# 03_ETHERNET_1_Gbps.net
KiCad netlist of a schematic drawn in Altium Designer
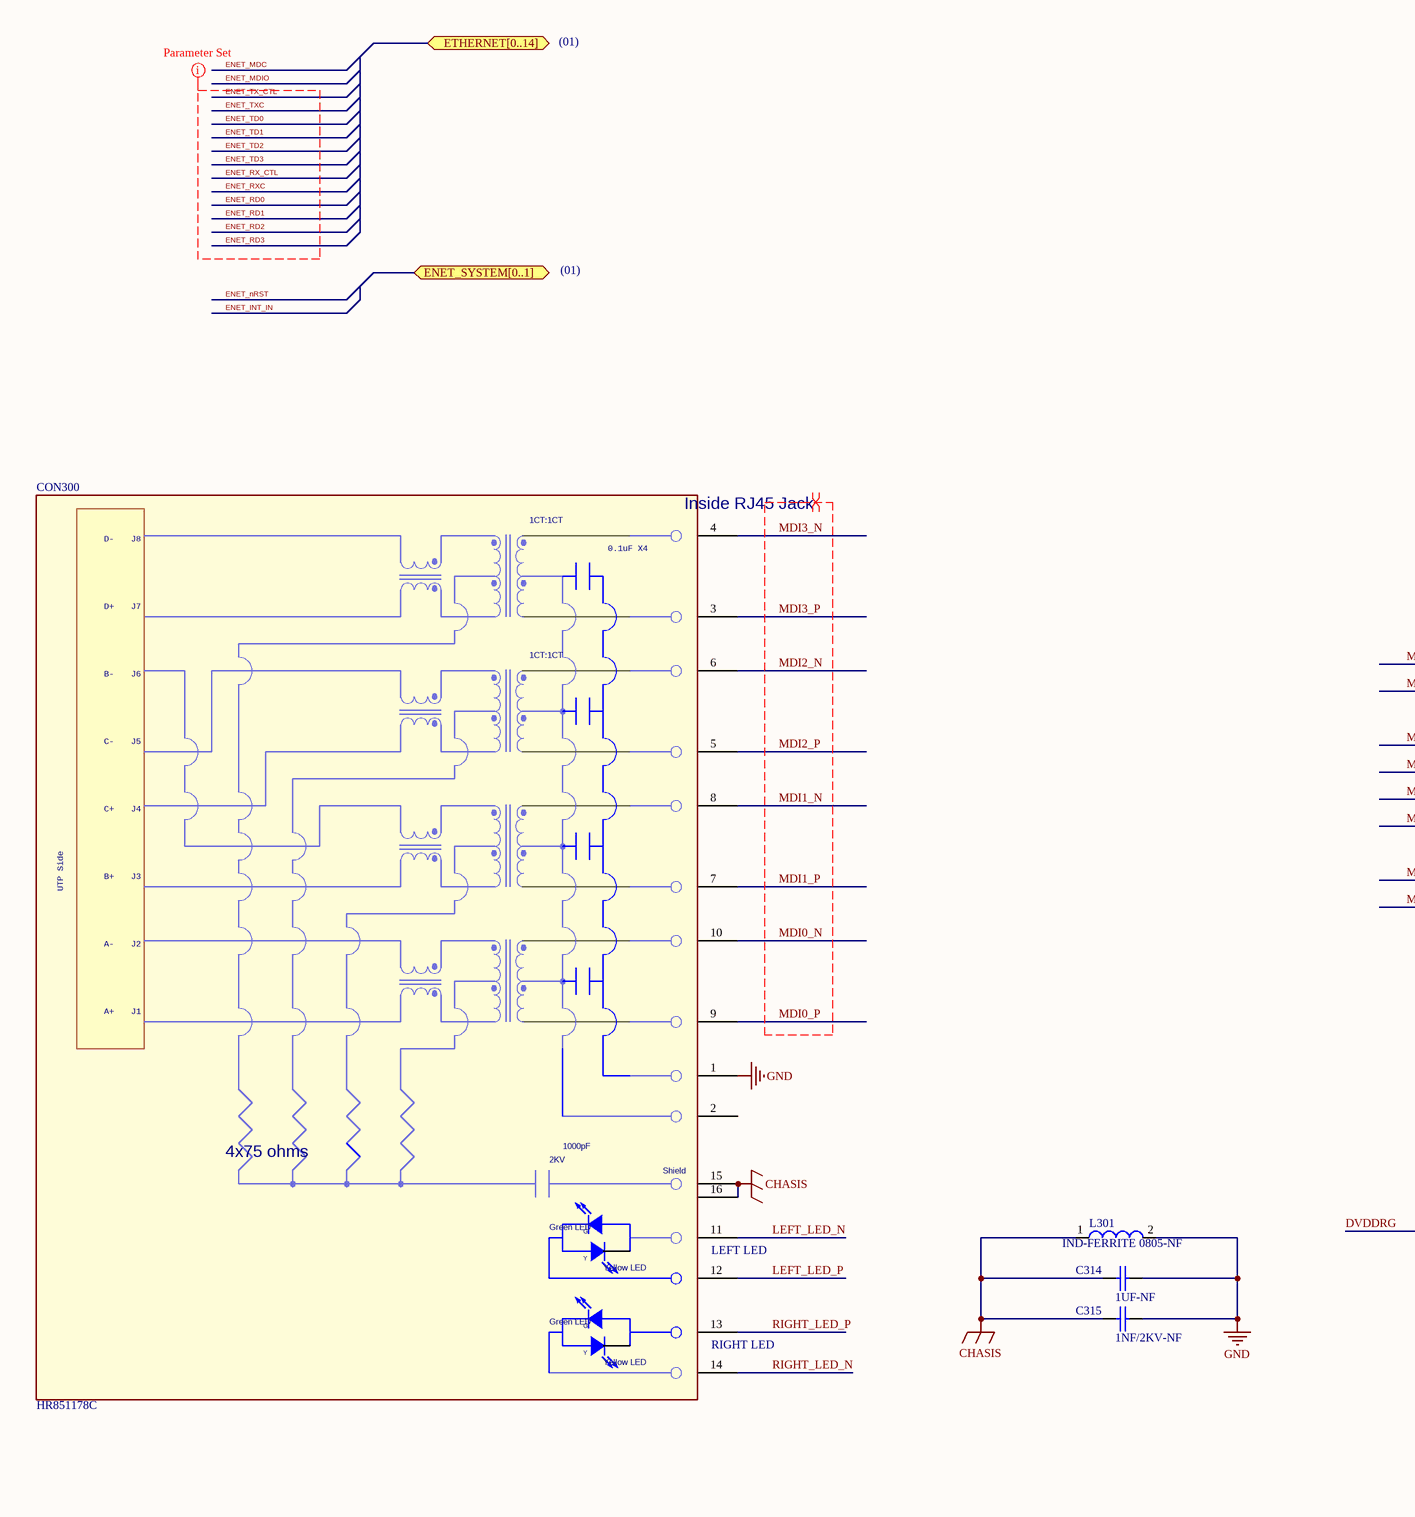
[diagram p0: 03 ETHERNET 1 Gbps.SchDoc, left]
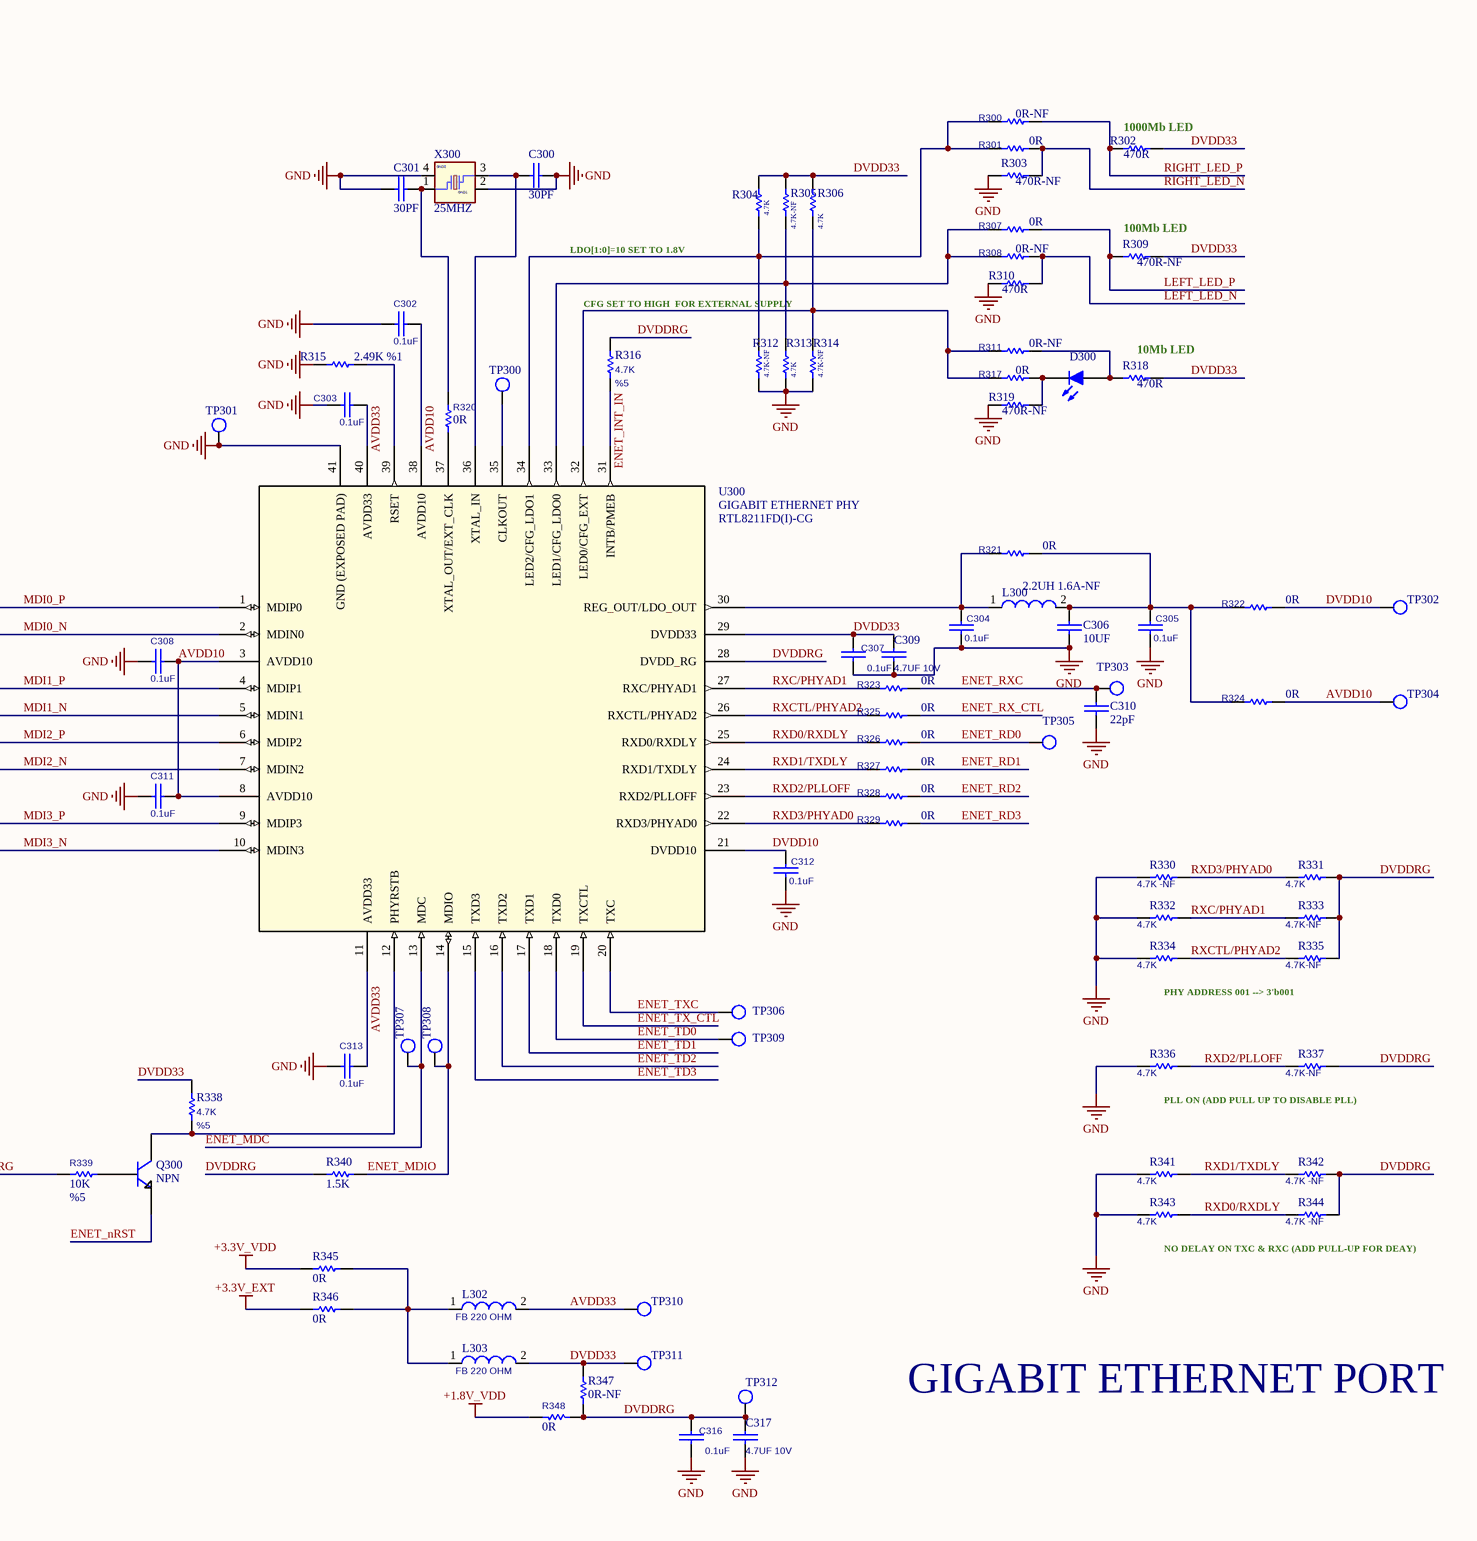
[diagram p1: 03 ETHERNET 1 Gbps.SchDoc, right]

(export (version "E")
  (design (tool "Eeschema 10.0.6"))
  (components
    (comp (ref "C300")
      (value "30PF")
      (footprint "0402_CC")
      (description "CAP CER 30PF 50V 5% C0G/NPO 0402")
      (fields (field (name "CREATED BY") "*") (field (name "CHECKED BY") "*"))
      (libsource (lib "ARETE_SCH") (part "CAP-CC0402JRNPO9BN300"))
    )
    (comp (ref "C301")
      (value "30PF")
      (footprint "0402_CC")
      (description "CAP CER 30PF 50V 5% C0G/NPO 0402")
      (fields (field (name "CREATED BY") "*") (field (name "CHECKED BY") "*"))
      (libsource (lib "ARETE_SCH") (part "CAP-CC0402JRNPO9BN300"))
    )
    (comp (ref "C302")
      (value "0.1uF")
      (footprint "0402_CC")
      (description "CAP VER 0.1UF 16V X7R 0402")
      (fields (field (name "CREATED BY") "LA") (field (name "CHECKED BY") "*"))
      (libsource (lib "ARETE_SCH") (part "CAP-CL05B104KO5NNNC"))
    )
    (comp (ref "C303")
      (value "0.1uF")
      (footprint "0402_CC")
      (description "CAP VER 0.1UF 16V X7R 0402")
      (fields (field (name "CREATED BY") "LA") (field (name "CHECKED BY") "*"))
      (libsource (lib "ARETE_SCH") (part "CAP-CL05B104KO5NNNC"))
    )
    (comp (ref "C304")
      (value "0.1uF")
      (footprint "0402_CC")
      (description "CAP VER 0.1UF 16V X7R 0402")
      (fields (field (name "CREATED BY") "LA") (field (name "CHECKED BY") "*"))
      (libsource (lib "ARETE_SCH") (part "CAP-CL05B104KO5NNNC"))
    )
    (comp (ref "C305")
      (value "0.1uF")
      (footprint "0402_CC")
      (description "CAP VER 0.1UF 16V X7R 0402")
      (fields (field (name "CREATED BY") "LA") (field (name "CHECKED BY") "*"))
      (libsource (lib "ARETE_SCH") (part "CAP-CL05B104KO5NNNC"))
    )
    (comp (ref "C306")
      (value "10UF")
      (footprint "0805")
      (description "CAP CER 10UF 6.3V X7R 0805")
      (fields (field (name "CREATED BY") "LA") (field (name "CHECKED BY") "*"))
      (libsource (lib "ARETE_SCH") (part "CAP-C0805C106M9RACAUTO"))
    )
    (comp (ref "C307")
      (value "0.1uF")
      (footprint "0402_CC")
      (description "CAP VER 0.1UF 16V X7R 0402")
      (fields (field (name "CREATED BY") "LA") (field (name "CHECKED BY") "*"))
      (libsource (lib "ARETE_SCH") (part "CAP-CL05B104KO5NNNC"))
    )
    (comp (ref "C308")
      (value "0.1uF")
      (footprint "0402_CC")
      (description "CAP VER 0.1UF 16V X7R 0402")
      (fields (field (name "CREATED BY") "LA") (field (name "CHECKED BY") "*"))
      (libsource (lib "ARETE_SCH") (part "CAP-CL05B104KO5NNNC"))
    )
    (comp (ref "C309")
      (value "4.7UF 10V")
      (footprint "0402_CC")
      (description "CAP CER 4.7UF 10V X5R 0402")
      (fields (field (name "CREATED BY") "EE") (field (name "CHECKED BY") "*"))
      (libsource (lib "ARETE_SCH") (part "CAP-CL05A475MP5NRNC"))
    )
    (comp (ref "C310")
      (value "22pF")
      (footprint "0402_CC")
      (description "CAP CER 22PF 50V C0G/NPO 0402")
      (fields (field (name "CREATED BY") "LA") (field (name "CHECKED BY") "*"))
      (libsource (lib "ARETE_SCH") (part "CAP-C0402C220K5GACTU"))
    )
    (comp (ref "C311")
      (value "0.1uF")
      (footprint "0402_CC")
      (description "CAP VER 0.1UF 16V X7R 0402")
      (fields (field (name "CREATED BY") "LA") (field (name "CHECKED BY") "*"))
      (libsource (lib "ARETE_SCH") (part "CAP-CL05B104KO5NNNC"))
    )
    (comp (ref "C312")
      (value "0.1uF")
      (footprint "0402_CC")
      (description "CAP VER 0.1UF 16V X7R 0402")
      (fields (field (name "CREATED BY") "LA") (field (name "CHECKED BY") "*"))
      (libsource (lib "ARETE_SCH") (part "CAP-CL05B104KO5NNNC"))
    )
    (comp (ref "C313")
      (value "0.1uF")
      (footprint "0402_CC")
      (description "CAP VER 0.1UF 16V X7R 0402")
      (fields (field (name "CREATED BY") "LA") (field (name "CHECKED BY") "*"))
      (libsource (lib "ARETE_SCH") (part "CAP-CL05B104KO5NNNC"))
    )
    (comp (ref "C314")
      (value "1UF-NF")
      (footprint "0805")
      (description "CAP CER 1UF 50V X7R 0805")
      (fields (field (name "CREATED BY") "*") (field (name "CHECKED BY") "*"))
      (libsource (lib "ARETE_SCH") (part "CAP-CL21B105KBFNNNG"))
    )
    (comp (ref "C315")
      (value "1NF/2KV-NF")
      (footprint "1206")
      (description "CAP CER 1NF 2KV 10% X7R SMD 1206")
      (fields (field (name "CREATED BY") "OKS") (field (name "CHECKED BY") "*"))
      (libsource (lib "ARETE_SCH") (part "CAP-1206GC102KAT2A"))
    )
    (comp (ref "C316")
      (value "0.1uF")
      (footprint "0402_CC")
      (description "CAP VER 0.1UF 16V X7R 0402")
      (fields (field (name "CREATED BY") "LA") (field (name "CHECKED BY") "*"))
      (libsource (lib "ARETE_SCH") (part "CAP-CL05B104KO5NNNC"))
    )
    (comp (ref "C317")
      (value "4.7UF 10V")
      (footprint "0402_CC")
      (description "CAP CER 4.7UF 10V X5R 0402")
      (fields (field (name "CREATED BY") "EE") (field (name "CHECKED BY") "*"))
      (libsource (lib "ARETE_SCH") (part "CAP-CL05A475MP5NRNC"))
    )
    (comp (ref "CON300")
      (value "HR851178C")
      (footprint "HR851178C")
      (description "GIGABIT ETHERNET CONN")
      (fields (field (name "CREATED BY") "EE") (field (name "CHECKED BY") "*"))
      (libsource (lib "ARETE_SCH") (part "CON-HR851178C"))
    )
    (comp (ref "D300")
      (value "GREEN")
      (footprint "0603_LED")
      (description "LED SMD 0603 SUPER GREEN")
      (fields (field (name "CREATED BY") "*") (field (name "CHECKED BY") "*"))
      (libsource (lib "ARETE_SCH") (part "LED-LTST-C190KRKT"))
    )
    (comp (ref "L300")
      (value "2.2UH 1.6A-NF")
      (footprint "2016")
      (description "FIXED IND 2.2UH 1.6A 154MOHM SMD")
      (fields (field (name "CREATED BY") "EE") (field (name "CHECKED BY") "*"))
      (libsource (lib "ARETE_V2_SCH") (part "IND-CIGT201610LM2R2MNE"))
    )
    (comp (ref "L301")
      (value "IND-FERRITE 0805-NF")
      (footprint "0805")
      (description "FERRITE BEAD 0805")
      (fields (field (name "CHECKED BY") "*"))
      (libsource (lib "ARETE_SCH") (part "IND-FERRITE 0805"))
    )
    (comp (ref "L302")
      (value "FB 220 OHM")
      (footprint "0603_RES")
      (description "Power Line Ferrite Bead 0603 (1608 Metric) 2.2A 50mOhmFERRITE BEAD 220 OHM 0603 1LN")
      (fields (field (name "CREATED BY") "E.E") (field (name "CHECKED BY") "*"))
      (libsource (lib "ARETE_SCH") (part "IND-MPZ1608S221ATA00"))
    )
    (comp (ref "L303")
      (value "FB 220 OHM")
      (footprint "0603_RES")
      (description "Power Line Ferrite Bead 0603 (1608 Metric) 2.2A 50mOhmFERRITE BEAD 220 OHM 0603 1LN")
      (fields (field (name "CREATED BY") "E.E") (field (name "CHECKED BY") "*"))
      (libsource (lib "ARETE_SCH") (part "IND-MPZ1608S221ATA00"))
    )
    (comp (ref "Q300")
      (value "NPN")
      (footprint "SOT23")
      (description "TRANS PNP 65V 0.1A SOT-23")
      (fields (field (name "CREATED BY") "LA") (field (name "CHECKED BY") "*"))
      (libsource (lib "ARETE_SCH") (part "TRANSISTOR-BC846"))
    )
    (comp (ref "R300")
      (value "0R-NF")
      (footprint "0402_RES")
      (description "RES 0 OHM JUMPER 1/16W 0402")
      (fields (field (name "CREATED BY") "LA") (field (name "CHECKED BY") "*"))
      (libsource (lib "ARETE_SCH") (part "RES-RMCF0402ZT0R00"))
    )
    (comp (ref "R301")
      (value "0R")
      (footprint "0402_RES")
      (description "RES 0 OHM JUMPER 1/16W 0402")
      (fields (field (name "CREATED BY") "LA") (field (name "CHECKED BY") "*"))
      (libsource (lib "ARETE_SCH") (part "RES-RMCF0402ZT0R00"))
    )
    (comp (ref "R302")
      (value "470R")
      (footprint "0402_RES")
      (description "RES SMD 470 OHM 1% 1/16W 0402")
      (fields
        (field (name "TOLERANCE") "%1")
        (field (name "CREATED BY") "LA")
        (field (name "CHECKED BY") "*")
      )
      (libsource (lib "ARETE_SCH") (part "RES-RC0402FR-07470R"))
    )
    (comp (ref "R303")
      (value "470R-NF")
      (footprint "0402_RES")
      (description "RES SMD 470 OHM 1% 1/16W 0402")
      (fields
        (field (name "TOLERANCE") "%1")
        (field (name "CREATED BY") "LA")
        (field (name "CHECKED BY") "*")
      )
      (libsource (lib "ARETE_SCH") (part "RES-RC0402FR-07470R"))
    )
    (comp (ref "R304")
      (value "4.7K")
      (footprint "0402_RES")
      (description "RES 4.7K OHM 5% 1/16W 0402")
      (fields
        (field (name "TOLERANCE") "%5")
        (field (name "CREATED BY") "LA")
        (field (name "CHECKED BY") "*")
      )
      (libsource (lib "ARETE_L") (part "RES-4.7K"))
    )
    (comp (ref "R305")
      (value "4.7K-NF")
      (footprint "0402_RES")
      (description "RES 4.7K OHM 5% 1/16W 0402")
      (fields
        (field (name "TOLERANCE") "%5")
        (field (name "CREATED BY") "LA")
        (field (name "CHECKED BY") "*")
      )
      (libsource (lib "ARETE_L") (part "RES-4.7K"))
    )
    (comp (ref "R306")
      (value "4.7K")
      (footprint "0402_RES")
      (description "RES 4.7K OHM 5% 1/16W 0402")
      (fields
        (field (name "TOLERANCE") "%5")
        (field (name "CREATED BY") "LA")
        (field (name "CHECKED BY") "*")
      )
      (libsource (lib "ARETE_L") (part "RES-4.7K"))
    )
    (comp (ref "R307")
      (value "0R")
      (footprint "0402_RES")
      (description "RES 0 OHM JUMPER 1/16W 0402")
      (fields (field (name "CREATED BY") "LA") (field (name "CHECKED BY") "*"))
      (libsource (lib "ARETE_SCH") (part "RES-RMCF0402ZT0R00"))
    )
    (comp (ref "R308")
      (value "0R-NF")
      (footprint "0402_RES")
      (description "RES 0 OHM JUMPER 1/16W 0402")
      (fields (field (name "CREATED BY") "LA") (field (name "CHECKED BY") "*"))
      (libsource (lib "ARETE_SCH") (part "RES-RMCF0402ZT0R00"))
    )
    (comp (ref "R309")
      (value "470R-NF")
      (footprint "0402_RES")
      (description "RES SMD 470 OHM 1% 1/16W 0402")
      (fields
        (field (name "TOLERANCE") "%1")
        (field (name "CREATED BY") "LA")
        (field (name "CHECKED BY") "*")
      )
      (libsource (lib "ARETE_SCH") (part "RES-RC0402FR-07470R"))
    )
    (comp (ref "R310")
      (value "470R")
      (footprint "0402_RES")
      (description "RES SMD 470 OHM 1% 1/16W 0402")
      (fields
        (field (name "TOLERANCE") "%1")
        (field (name "CREATED BY") "LA")
        (field (name "CHECKED BY") "*")
      )
      (libsource (lib "ARETE_SCH") (part "RES-RC0402FR-07470R"))
    )
    (comp (ref "R311")
      (value "0R-NF")
      (footprint "0402_RES")
      (description "RES 0 OHM JUMPER 1/16W 0402")
      (fields (field (name "CREATED BY") "LA") (field (name "CHECKED BY") "*"))
      (libsource (lib "ARETE_SCH") (part "RES-RMCF0402ZT0R00"))
    )
    (comp (ref "R312")
      (value "4.7K-NF")
      (footprint "0402_RES")
      (description "RES 4.7K OHM 5% 1/16W 0402")
      (fields
        (field (name "TOLERANCE") "%5")
        (field (name "CREATED BY") "LA")
        (field (name "CHECKED BY") "*")
      )
      (libsource (lib "ARETE_L") (part "RES-4.7K"))
    )
    (comp (ref "R313")
      (value "4.7K")
      (footprint "0402_RES")
      (description "RES 4.7K OHM 5% 1/16W 0402")
      (fields
        (field (name "TOLERANCE") "%5")
        (field (name "CREATED BY") "LA")
        (field (name "CHECKED BY") "*")
      )
      (libsource (lib "ARETE_L") (part "RES-4.7K"))
    )
    (comp (ref "R314")
      (value "4.7K-NF")
      (footprint "0402_RES")
      (description "RES 4.7K OHM 5% 1/16W 0402")
      (fields
        (field (name "TOLERANCE") "%5")
        (field (name "CREATED BY") "LA")
        (field (name "CHECKED BY") "*")
      )
      (libsource (lib "ARETE_L") (part "RES-4.7K"))
    )
    (comp (ref "R315")
      (value "2.49K %1")
      (footprint "0603_RES")
      (description "RES 2.49K OHM 1% 1/10W 0603")
      (fields (field (name "CREATED BY") "*") (field (name "CHECKED BY") "*"))
      (libsource (lib "ARETE_SCH") (part "RES-RMCF0603FT2K49"))
    )
    (comp (ref "R316")
      (value "4.7K")
      (footprint "0402_RES")
      (description "RES 4.7K OHM 5% 1/16W 0402")
      (fields
        (field (name "TOLERANCE") "%5")
        (field (name "CREATED BY") "LA")
        (field (name "CHECKED BY") "*")
      )
      (libsource (lib "ARETE_SCH") (part "RES-4.7K"))
    )
    (comp (ref "R317")
      (value "0R")
      (footprint "0402_RES")
      (description "RES 0 OHM JUMPER 1/16W 0402")
      (fields (field (name "CREATED BY") "LA") (field (name "CHECKED BY") "*"))
      (libsource (lib "ARETE_SCH") (part "RES-RMCF0402ZT0R00"))
    )
    (comp (ref "R318")
      (value "470R")
      (footprint "0402_RES")
      (description "RES SMD 470 OHM 1% 1/16W 0402")
      (fields
        (field (name "TOLERANCE") "%1")
        (field (name "CREATED BY") "LA")
        (field (name "CHECKED BY") "*")
      )
      (libsource (lib "ARETE_SCH") (part "RES-RC0402FR-07470R"))
    )
    (comp (ref "R319")
      (value "470R-NF")
      (footprint "0402_RES")
      (description "RES SMD 470 OHM 1% 1/16W 0402")
      (fields
        (field (name "TOLERANCE") "%1")
        (field (name "CREATED BY") "LA")
        (field (name "CHECKED BY") "*")
      )
      (libsource (lib "ARETE_SCH") (part "RES-RC0402FR-07470R"))
    )
    (comp (ref "R320")
      (value "0R")
      (footprint "0402_RES")
      (description "RES 0 OHM JUMPER 1/16W 0402")
      (fields (field (name "CREATED BY") "LA") (field (name "CHECKED BY") "*"))
      (libsource (lib "ARETE_SCH") (part "RES-RMCF0402ZT0R00"))
    )
    (comp (ref "R321")
      (value "0R")
      (footprint "0402_RES")
      (description "RES 0 OHM JUMPER 1/16W 0402")
      (fields (field (name "CREATED BY") "LA") (field (name "CHECKED BY") "*"))
      (libsource (lib "ARETE_SCH") (part "RES-RMCF0402ZT0R00"))
    )
    (comp (ref "R322")
      (value "0R")
      (footprint "0402_RES")
      (description "RES 0 OHM JUMPER 1/16W 0402")
      (fields (field (name "CREATED BY") "LA") (field (name "CHECKED BY") "*"))
      (libsource (lib "ARETE_SCH") (part "RES-RMCF0402ZT0R00"))
    )
    (comp (ref "R323")
      (value "0R")
      (footprint "0402_RES")
      (description "RES 0 OHM JUMPER 1/16W 0402")
      (fields (field (name "CREATED BY") "LA") (field (name "CHECKED BY") "*"))
      (libsource (lib "ARETE_SCH") (part "RES-RMCF0402ZT0R00"))
    )
    (comp (ref "R324")
      (value "0R")
      (footprint "0402_RES")
      (description "RES 0 OHM JUMPER 1/16W 0402")
      (fields (field (name "CREATED BY") "LA") (field (name "CHECKED BY") "*"))
      (libsource (lib "ARETE_SCH") (part "RES-RMCF0402ZT0R00"))
    )
    (comp (ref "R325")
      (value "0R")
      (footprint "0402_RES")
      (description "RES 0 OHM JUMPER 1/16W 0402")
      (fields (field (name "CREATED BY") "LA") (field (name "CHECKED BY") "*"))
      (libsource (lib "ARETE_SCH") (part "RES-RMCF0402ZT0R00"))
    )
    (comp (ref "R326")
      (value "0R")
      (footprint "0402_RES")
      (description "RES 0 OHM JUMPER 1/16W 0402")
      (fields (field (name "CREATED BY") "LA") (field (name "CHECKED BY") "*"))
      (libsource (lib "ARETE_SCH") (part "RES-RMCF0402ZT0R00"))
    )
    (comp (ref "R327")
      (value "0R")
      (footprint "0402_RES")
      (description "RES 0 OHM JUMPER 1/16W 0402")
      (fields (field (name "CREATED BY") "LA") (field (name "CHECKED BY") "*"))
      (libsource (lib "ARETE_SCH") (part "RES-RMCF0402ZT0R00"))
    )
    (comp (ref "R328")
      (value "0R")
      (footprint "0402_RES")
      (description "RES 0 OHM JUMPER 1/16W 0402")
      (fields (field (name "CREATED BY") "LA") (field (name "CHECKED BY") "*"))
      (libsource (lib "ARETE_SCH") (part "RES-RMCF0402ZT0R00"))
    )
    (comp (ref "R329")
      (value "0R")
      (footprint "0402_RES")
      (description "RES 0 OHM JUMPER 1/16W 0402")
      (fields (field (name "CREATED BY") "LA") (field (name "CHECKED BY") "*"))
      (libsource (lib "ARETE_SCH") (part "RES-RMCF0402ZT0R00"))
    )
    (comp (ref "R330")
      (value "4.7K -NF")
      (footprint "0402_RES")
      (description "RES 4.7K OHM 5% 1/16W 0402")
      (fields
        (field (name "TOLERANCE") "%5")
        (field (name "CREATED BY") "LA")
        (field (name "CHECKED BY") "*")
      )
      (libsource (lib "ARETE_SCH") (part "RES-4.7K"))
    )
    (comp (ref "R331")
      (value "4.7K")
      (footprint "0402_RES")
      (description "RES 4.7K OHM 5% 1/16W 0402")
      (fields
        (field (name "TOLERANCE") "%5")
        (field (name "CREATED BY") "LA")
        (field (name "CHECKED BY") "*")
      )
      (libsource (lib "ARETE_SCH") (part "RES-4.7K"))
    )
    (comp (ref "R332")
      (value "4.7K")
      (footprint "0402_RES")
      (description "RES 4.7K OHM 5% 1/16W 0402")
      (fields
        (field (name "TOLERANCE") "%5")
        (field (name "CREATED BY") "LA")
        (field (name "CHECKED BY") "*")
      )
      (libsource (lib "ARETE_SCH") (part "RES-4.7K"))
    )
    (comp (ref "R333")
      (value "4.7K-NF")
      (footprint "0402_RES")
      (description "RES 4.7K OHM 5% 1/16W 0402")
      (fields
        (field (name "TOLERANCE") "%5")
        (field (name "CREATED BY") "LA")
        (field (name "CHECKED BY") "*")
      )
      (libsource (lib "ARETE_SCH") (part "RES-4.7K"))
    )
    (comp (ref "R334")
      (value "4.7K")
      (footprint "0402_RES")
      (description "RES 4.7K OHM 5% 1/16W 0402")
      (fields
        (field (name "TOLERANCE") "%5")
        (field (name "CREATED BY") "LA")
        (field (name "CHECKED BY") "*")
      )
      (libsource (lib "ARETE_SCH") (part "RES-4.7K"))
    )
    (comp (ref "R335")
      (value "4.7K-NF")
      (footprint "0402_RES")
      (description "RES 4.7K OHM 5% 1/16W 0402")
      (fields
        (field (name "TOLERANCE") "%5")
        (field (name "CREATED BY") "LA")
        (field (name "CHECKED BY") "*")
      )
      (libsource (lib "ARETE_SCH") (part "RES-4.7K"))
    )
    (comp (ref "R336")
      (value "4.7K")
      (footprint "0402_RES")
      (description "RES 4.7K OHM 5% 1/16W 0402")
      (fields
        (field (name "TOLERANCE") "%5")
        (field (name "CREATED BY") "LA")
        (field (name "CHECKED BY") "*")
      )
      (libsource (lib "ARETE_SCH") (part "RES-4.7K"))
    )
    (comp (ref "R337")
      (value "4.7K-NF")
      (footprint "0402_RES")
      (description "RES 4.7K OHM 5% 1/16W 0402")
      (fields
        (field (name "TOLERANCE") "%5")
        (field (name "CREATED BY") "LA")
        (field (name "CHECKED BY") "*")
      )
      (libsource (lib "ARETE_SCH") (part "RES-4.7K"))
    )
    (comp (ref "R338")
      (value "4.7K")
      (footprint "0402_RES")
      (description "RES 4.7K OHM 5% 1/16W 0402")
      (fields
        (field (name "TOLERANCE") "%5")
        (field (name "CREATED BY") "LA")
        (field (name "CHECKED BY") "*")
      )
      (libsource (lib "ARETE_SCH") (part "RES-4.7K"))
    )
    (comp (ref "R339")
      (value "10K")
      (footprint "0402_RES")
      (description "RES 10K OHM 5% 1/16W 0402")
      (fields
        (field (name "TOLERANCE") "%5")
        (field (name "CREATED BY") "LA")
        (field (name "CHECKED BY") "*")
      )
      (libsource (lib "ARETE_SCH") (part "RES-RMCF0402JT10K0"))
    )
    (comp (ref "R340")
      (value "1.5K")
      (footprint "0402_RES")
      (description "RES SMD 1.5K OHM 5% 1/16W 0402 AUTOMOTIVE")
      (fields
        (field (name "TOLERANCE") "%5")
        (field (name "CREATED BY") "OKS")
        (field (name "CHECKED BY") "*")
      )
      (libsource (lib "ARETE_SCH") (part "RES-RMCF0402JT1K50"))
    )
    (comp (ref "R341")
      (value "4.7K")
      (footprint "0402_RES")
      (description "RES 4.7K OHM 5% 1/16W 0402")
      (fields
        (field (name "TOLERANCE") "%5")
        (field (name "CREATED BY") "LA")
        (field (name "CHECKED BY") "*")
      )
      (libsource (lib "ARETE_SCH") (part "RES-4.7K"))
    )
    (comp (ref "R342")
      (value "4.7K -NF")
      (footprint "0402_RES")
      (description "RES 4.7K OHM 5% 1/16W 0402")
      (fields
        (field (name "TOLERANCE") "%5")
        (field (name "CREATED BY") "LA")
        (field (name "CHECKED BY") "*")
      )
      (libsource (lib "ARETE_SCH") (part "RES-4.7K"))
    )
    (comp (ref "R343")
      (value "4.7K")
      (footprint "0402_RES")
      (description "RES 4.7K OHM 5% 1/16W 0402")
      (fields
        (field (name "TOLERANCE") "%5")
        (field (name "CREATED BY") "LA")
        (field (name "CHECKED BY") "*")
      )
      (libsource (lib "ARETE_SCH") (part "RES-4.7K"))
    )
    (comp (ref "R344")
      (value "4.7K -NF")
      (footprint "0402_RES")
      (description "RES 4.7K OHM 5% 1/16W 0402")
      (fields
        (field (name "TOLERANCE") "%5")
        (field (name "CREATED BY") "LA")
        (field (name "CHECKED BY") "*")
      )
      (libsource (lib "ARETE_SCH") (part "RES-4.7K"))
    )
    (comp (ref "R345")
      (value "0R")
      (footprint "0603_RES")
      (description "RES 0R OHM JUMPER 1/10W 0603")
      (fields (field (name "CREATED BY") "LA") (field (name "CHECKED BY") "*"))
      (libsource (lib "ARETE_SCH") (part "RES-RC0603FR-070RL"))
    )
    (comp (ref "R346")
      (value "0R")
      (footprint "0603_RES")
      (description "RES 0R OHM JUMPER 1/10W 0603")
      (fields (field (name "CREATED BY") "LA") (field (name "CHECKED BY") "*"))
      (libsource (lib "ARETE_SCH") (part "RES-RC0603FR-070RL"))
    )
    (comp (ref "R347")
      (value "0R-NF")
      (footprint "0603_RES")
      (description "RES 0R OHM JUMPER 1/10W 0603")
      (fields (field (name "CREATED BY") "LA") (field (name "CHECKED BY") "*"))
      (libsource (lib "ARETE_SCH") (part "RES-RC0603FR-070RL"))
    )
    (comp (ref "R348")
      (value "0R")
      (footprint "0402_RES")
      (description "RES 0 OHM JUMPER 1/16W 0402")
      (fields (field (name "CREATED BY") "LA") (field (name "CHECKED BY") "*"))
      (libsource (lib "ARETE_SCH") (part "RES-RMCF0402ZT0R00"))
    )
    (comp (ref "TP300")
      (value "TEST POINT 35")
      (footprint "testpoint_15")
      (libsource (lib "ARETE_SCH") (part "TEST POINT 35"))
    )
    (comp (ref "TP301")
      (value "TEST POINT 35")
      (footprint "testpoint_15")
      (libsource (lib "ARETE_SCH") (part "TEST POINT 35"))
    )
    (comp (ref "TP302")
      (value "TEST POINT 35")
      (footprint "testpoint_15")
      (libsource (lib "ARETE_SCH") (part "TEST POINT 35"))
    )
    (comp (ref "TP303")
      (value "TEST POINT 35")
      (footprint "testpoint_15")
      (libsource (lib "ARETE_SCH") (part "TEST POINT 35"))
    )
    (comp (ref "TP304")
      (value "TEST POINT 35")
      (footprint "testpoint_15")
      (libsource (lib "ARETE_SCH") (part "TEST POINT 35"))
    )
    (comp (ref "TP305")
      (value "TEST POINT 35")
      (footprint "testpoint_15")
      (libsource (lib "ARETE_SCH") (part "TEST POINT 35"))
    )
    (comp (ref "TP306")
      (value "TEST POINT 35")
      (footprint "testpoint_15")
      (libsource (lib "ARETE_SCH") (part "TEST POINT 35"))
    )
    (comp (ref "TP307")
      (value "TEST POINT 35")
      (footprint "testpoint_15")
      (libsource (lib "ARETE_SCH") (part "TEST POINT 35"))
    )
    (comp (ref "TP308")
      (value "TEST POINT 35")
      (footprint "testpoint_15")
      (libsource (lib "ARETE_SCH") (part "TEST POINT 35"))
    )
    (comp (ref "TP309")
      (value "TEST POINT 35")
      (footprint "testpoint_15")
      (libsource (lib "ARETE_SCH") (part "TEST POINT 35"))
    )
    (comp (ref "TP310")
      (value "TEST POINT 35")
      (footprint "testpoint_15")
      (libsource (lib "ARETE_SCH") (part "TEST POINT 35"))
    )
    (comp (ref "TP311")
      (value "TEST POINT 35")
      (footprint "testpoint_15")
      (libsource (lib "ARETE_SCH") (part "TEST POINT 35"))
    )
    (comp (ref "TP312")
      (value "TEST POINT 35")
      (footprint "testpoint_15")
      (libsource (lib "ARETE_SCH") (part "TEST POINT 35"))
    )
    (comp (ref "U300")
      (value "GIGABIT ETHERNET PHY")
      (footprint "Quad40")
      (description "IC PHY GIGABIT ETHERNET IEEE 802.3AB 40-QFN (5x5)")
      (fields
        (field (name "MANUFACTURER PART NUMBER-1") "RTL8211FD(I)-CG")
        (field (name "CREATED BY") "OKS")
        (field (name "CHECKED BY") "*")
      )
      (libsource (lib "ARETE_SCH") (part "IC-RTL8211FD(I)-CG"))
    )
    (comp (ref "X300")
      (value "25MHZ")
      (footprint "XTLOSC4_3P2X2P5MM_SM")
      (description "CRYSTAL 25.0000MHZ 20PF 10PPM SMD")
      (fields (field (name "CREATED BY") "OKS") (field (name "CHECKED BY") "*"))
      (libsource (lib "ARETE_SCH") (part "XTAL-TSX-3225 25.0000MF18X-G"))
    )
  )
  (nets
    (net (code "18") (name "+1.8V_VDD") (class "Default")
      (node (ref "R348") (pin "1") (pinfunction "1_1") (pintype "passive"))
    )
    (net (code "19") (name "+3.3V_EXT") (class "Default")
      (node (ref "R346") (pin "1") (pinfunction "1_1") (pintype "passive"))
    )
    (net (code "20") (name "+3.3V_VDD") (class "Default")
      (node (ref "R345") (pin "1") (pinfunction "1_1") (pintype "passive"))
    )
    (net (code "21") (name "/AVDD10") (class "Default")
      (node (ref "C302") (pin "2") (pinfunction "2_2") (pintype "passive"))
      (node (ref "C308") (pin "2") (pinfunction "2_2") (pintype "passive"))
      (node (ref "C311") (pin "2") (pinfunction "2_2") (pintype "passive"))
      (node (ref "R324") (pin "1") (pinfunction "1_1") (pintype "passive"))
      (node (ref "TP304") (pin "1") (pinfunction "1_1") (pintype "passive"))
      (node (ref "U300") (pin "3") (pinfunction "AVDD10_3") (pintype "power_in"))
      (node (ref "U300") (pin "38") (pinfunction "AVDD10_38") (pintype "power_in"))
      (node (ref "U300") (pin "8") (pinfunction "AVDD10_8") (pintype "power_in"))
    )
    (net (code "22") (name "/AVDD33") (class "Default")
      (node (ref "C303") (pin "2") (pinfunction "2_2") (pintype "passive"))
      (node (ref "C313") (pin "2") (pinfunction "2_2") (pintype "passive"))
      (node (ref "L302") (pin "2") (pinfunction "2_2") (pintype "passive"))
      (node (ref "TP310") (pin "1") (pinfunction "1_1") (pintype "passive"))
      (node (ref "U300") (pin "11") (pinfunction "AVDD33_11") (pintype "power_in"))
      (node (ref "U300") (pin "40") (pinfunction "AVDD33_40") (pintype "power_in"))
    )
    (net (code "23") (name "/DVDD10") (class "Default")
      (node (ref "C312") (pin "1") (pinfunction "1_1") (pintype "passive"))
      (node (ref "R322") (pin "1") (pinfunction "1_1") (pintype "passive"))
      (node (ref "TP302") (pin "1") (pinfunction "1_1") (pintype "passive"))
      (node (ref "U300") (pin "21") (pinfunction "DVDD10_21") (pintype "power_in"))
    )
    (net (code "24") (name "/DVDD33") (class "Default")
      (node (ref "C307") (pin "1") (pinfunction "1_1") (pintype "passive"))
      (node (ref "C309") (pin "1") (pinfunction "1_1") (pintype "passive"))
      (node (ref "L303") (pin "2") (pinfunction "2_2") (pintype "passive"))
      (node (ref "R302") (pin "2") (pinfunction "2_2") (pintype "passive"))
      (node (ref "R304") (pin "1") (pinfunction "1_1") (pintype "passive"))
      (node (ref "R305") (pin "1") (pinfunction "1_1") (pintype "passive"))
      (node (ref "R306") (pin "1") (pinfunction "1_1") (pintype "passive"))
      (node (ref "R309") (pin "2") (pinfunction "2_2") (pintype "passive"))
      (node (ref "R318") (pin "2") (pinfunction "2_2") (pintype "passive"))
      (node (ref "R338") (pin "2") (pinfunction "2_2") (pintype "passive"))
      (node (ref "R347") (pin "2") (pinfunction "2_2") (pintype "passive"))
      (node (ref "TP311") (pin "1") (pinfunction "1_1") (pintype "passive"))
      (node (ref "U300") (pin "29") (pinfunction "DVDD33_29") (pintype "power_in"))
    )
    (net (code "25") (name "/DVDDRG") (class "Default")
      (node (ref "C316") (pin "1") (pinfunction "1_1") (pintype "passive"))
      (node (ref "C317") (pin "1") (pinfunction "1_1") (pintype "passive"))
      (node (ref "R316") (pin "2") (pinfunction "2_2") (pintype "passive"))
      (node (ref "R331") (pin "1") (pinfunction "1_1") (pintype "passive"))
      (node (ref "R333") (pin "1") (pinfunction "1_1") (pintype "passive"))
      (node (ref "R335") (pin "1") (pinfunction "1_1") (pintype "passive"))
      (node (ref "R337") (pin "1") (pinfunction "1_1") (pintype "passive"))
      (node (ref "R339") (pin "2") (pinfunction "2_2") (pintype "passive"))
      (node (ref "R340") (pin "1") (pinfunction "1_1") (pintype "passive"))
      (node (ref "R342") (pin "1") (pinfunction "1_1") (pintype "passive"))
      (node (ref "R344") (pin "1") (pinfunction "1_1") (pintype "passive"))
      (node (ref "R347") (pin "1") (pinfunction "1_1") (pintype "passive"))
      (node (ref "R348") (pin "2") (pinfunction "2_2") (pintype "passive"))
      (node (ref "TP312") (pin "1") (pinfunction "1_1") (pintype "passive"))
      (node (ref "U300") (pin "28") (pinfunction "DVDD_RG_28") (pintype "power_in"))
    )
    (net (code "26") (name "/ENET_INT_IN") (class "Default")
      (node (ref "R316") (pin "1") (pinfunction "1_1") (pintype "passive"))
      (node (ref "U300") (pin "31") (pinfunction "INTB/PMEB_31") (pintype "output"))
    )
    (net (code "27") (name "/ENET_MDC") (class "Default")
      (node (ref "TP307") (pin "1") (pinfunction "1_1") (pintype "passive"))
      (node (ref "U300") (pin "13") (pinfunction "MDC_13") (pintype "input"))
    )
    (net (code "28") (name "/ENET_MDIO") (class "Default")
      (node (ref "R340") (pin "2") (pinfunction "2_2") (pintype "passive"))
      (node (ref "TP308") (pin "1") (pinfunction "1_1") (pintype "passive"))
      (node (ref "U300") (pin "14") (pinfunction "MDIO_14") (pintype "bidirectional"))
    )
    (net (code "29") (name "/ENET_RD0") (class "Default")
      (node (ref "R326") (pin "1") (pinfunction "1_1") (pintype "passive"))
      (node (ref "TP305") (pin "1") (pinfunction "1_1") (pintype "passive"))
    )
    (net (code "30") (name "/ENET_RD1") (class "Default")
      (node (ref "R327") (pin "1") (pinfunction "1_1") (pintype "passive"))
    )
    (net (code "31") (name "/ENET_RD2") (class "Default")
      (node (ref "R328") (pin "1") (pinfunction "1_1") (pintype "passive"))
    )
    (net (code "32") (name "/ENET_RD3") (class "Default")
      (node (ref "R329") (pin "1") (pinfunction "1_1") (pintype "passive"))
    )
    (net (code "33") (name "/ENET_RXC") (class "Default")
      (node (ref "C310") (pin "1") (pinfunction "1_1") (pintype "passive"))
      (node (ref "R323") (pin "1") (pinfunction "1_1") (pintype "passive"))
      (node (ref "TP303") (pin "1") (pinfunction "1_1") (pintype "passive"))
    )
    (net (code "34") (name "/ENET_RX_CTL") (class "Default")
      (node (ref "R325") (pin "1") (pinfunction "1_1") (pintype "passive"))
    )
    (net (code "36") (name "/ENET_TD0") (class "Default")
      (node (ref "TP309") (pin "1") (pinfunction "1_1") (pintype "passive"))
      (node (ref "U300") (pin "18") (pinfunction "TXD0_18") (pintype "input"))
    )
    (net (code "37") (name "/ENET_TD1") (class "Default")
      (node (ref "U300") (pin "17") (pinfunction "TXD1_17") (pintype "input"))
    )
    (net (code "38") (name "/ENET_TD2") (class "Default")
      (node (ref "U300") (pin "16") (pinfunction "TXD2_16") (pintype "input"))
    )
    (net (code "39") (name "/ENET_TD3") (class "Default")
      (node (ref "U300") (pin "15") (pinfunction "TXD3_15") (pintype "input"))
    )
    (net (code "40") (name "/ENET_TXC") (class "Default")
      (node (ref "TP306") (pin "1") (pinfunction "1_1") (pintype "passive"))
      (node (ref "U300") (pin "20") (pinfunction "TXC_20") (pintype "input"))
    )
    (net (code "41") (name "/ENET_TX_CTL") (class "Default")
      (node (ref "U300") (pin "19") (pinfunction "TXCTL_19") (pintype "input"))
    )
    (net (code "42") (name "/ENET_nRST") (class "Default")
      (node (ref "Q300") (pin "2") (pinfunction "E_2") (pintype "passive"))
    )
    (net (code "44") (name "/LEFT_LED_N") (class "Default")
      (node (ref "CON300") (pin "11") (pinfunction "11_11") (pintype "passive"))
      (node (ref "R308") (pin "1") (pinfunction "1_1") (pintype "passive"))
      (node (ref "R310") (pin "2") (pinfunction "2_2") (pintype "passive"))
    )
    (net (code "45") (name "/LEFT_LED_P") (class "Default")
      (node (ref "CON300") (pin "12") (pinfunction "12_12") (pintype "passive"))
      (node (ref "R307") (pin "1") (pinfunction "1_1") (pintype "passive"))
      (node (ref "R309") (pin "1") (pinfunction "1_1") (pintype "passive"))
    )
    (net (code "46") (name "/MDI0_N") (class "Default")
      (node (ref "CON300") (pin "10") (pinfunction "10_10") (pintype "passive"))
      (node (ref "U300") (pin "2") (pinfunction "MDIN0_2") (pintype "bidirectional"))
    )
    (net (code "47") (name "/MDI0_P") (class "Default")
      (node (ref "CON300") (pin "9") (pinfunction "9_9") (pintype "passive"))
      (node (ref "U300") (pin "1") (pinfunction "MDIP0_1") (pintype "bidirectional"))
    )
    (net (code "48") (name "/MDI1_N") (class "Default")
      (node (ref "CON300") (pin "8") (pinfunction "8_8") (pintype "passive"))
      (node (ref "U300") (pin "5") (pinfunction "MDIN1_5") (pintype "bidirectional"))
    )
    (net (code "49") (name "/MDI1_P") (class "Default")
      (node (ref "CON300") (pin "7") (pinfunction "7_7") (pintype "passive"))
      (node (ref "U300") (pin "4") (pinfunction "MDIP1_4") (pintype "bidirectional"))
    )
    (net (code "50") (name "/MDI2_N") (class "Default")
      (node (ref "CON300") (pin "6") (pinfunction "6_6") (pintype "passive"))
      (node (ref "U300") (pin "7") (pinfunction "MDIN2_7") (pintype "bidirectional"))
    )
    (net (code "51") (name "/MDI2_P") (class "Default")
      (node (ref "CON300") (pin "5") (pinfunction "5_5") (pintype "passive"))
      (node (ref "U300") (pin "6") (pinfunction "MDIP2_6") (pintype "bidirectional"))
    )
    (net (code "52") (name "/MDI3_N") (class "Default")
      (node (ref "CON300") (pin "4") (pinfunction "4_4") (pintype "passive"))
      (node (ref "U300") (pin "10") (pinfunction "MDIN3_10") (pintype "bidirectional"))
    )
    (net (code "53") (name "/MDI3_P") (class "Default")
      (node (ref "CON300") (pin "3") (pinfunction "3_3") (pintype "passive"))
      (node (ref "U300") (pin "9") (pinfunction "MDIP3_9") (pintype "bidirectional"))
    )
    (net (code "54") (name "/RIGHT_LED_N") (class "Default")
      (node (ref "CON300") (pin "14") (pinfunction "14_14") (pintype "passive"))
      (node (ref "R301") (pin "1") (pinfunction "1_1") (pintype "passive"))
      (node (ref "R303") (pin "2") (pinfunction "2_2") (pintype "passive"))
    )
    (net (code "55") (name "/RIGHT_LED_P") (class "Default")
      (node (ref "CON300") (pin "13") (pinfunction "13_13") (pintype "passive"))
      (node (ref "R300") (pin "1") (pinfunction "1_1") (pintype "passive"))
      (node (ref "R302") (pin "1") (pinfunction "1_1") (pintype "passive"))
    )
    (net (code "56") (name "/RXCTL{slash}PHYAD2") (class "Default")
      (node (ref "R325") (pin "2") (pinfunction "2_2") (pintype "passive"))
      (node (ref "R334") (pin "1") (pinfunction "1_1") (pintype "passive"))
      (node (ref "R335") (pin "2") (pinfunction "2_2") (pintype "passive"))
      (node (ref "U300") (pin "26") (pinfunction "RXCTL/PHYAD2_26") (pintype "output"))
    )
    (net (code "57") (name "/RXC{slash}PHYAD1") (class "Default")
      (node (ref "R323") (pin "2") (pinfunction "2_2") (pintype "passive"))
      (node (ref "R332") (pin "1") (pinfunction "1_1") (pintype "passive"))
      (node (ref "R333") (pin "2") (pinfunction "2_2") (pintype "passive"))
      (node (ref "U300") (pin "27") (pinfunction "RXC/PHYAD1_27") (pintype "output"))
    )
    (net (code "58") (name "/RXD0{slash}RXDLY") (class "Default")
      (node (ref "R326") (pin "2") (pinfunction "2_2") (pintype "passive"))
      (node (ref "R343") (pin "1") (pinfunction "1_1") (pintype "passive"))
      (node (ref "R344") (pin "2") (pinfunction "2_2") (pintype "passive"))
      (node (ref "U300") (pin "25") (pinfunction "RXD0/RXDLY_25") (pintype "output"))
    )
    (net (code "59") (name "/RXD1{slash}TXDLY") (class "Default")
      (node (ref "R327") (pin "2") (pinfunction "2_2") (pintype "passive"))
      (node (ref "R341") (pin "1") (pinfunction "1_1") (pintype "passive"))
      (node (ref "R342") (pin "2") (pinfunction "2_2") (pintype "passive"))
      (node (ref "U300") (pin "24") (pinfunction "RXD1/TXDLY_24") (pintype "output"))
    )
    (net (code "60") (name "/RXD2{slash}PLLOFF") (class "Default")
      (node (ref "R328") (pin "2") (pinfunction "2_2") (pintype "passive"))
      (node (ref "R336") (pin "1") (pinfunction "1_1") (pintype "passive"))
      (node (ref "R337") (pin "2") (pinfunction "2_2") (pintype "passive"))
      (node (ref "U300") (pin "23") (pinfunction "RXD2/PLLOFF_23") (pintype "output"))
    )
    (net (code "61") (name "/RXD3{slash}PHYAD0") (class "Default")
      (node (ref "R329") (pin "2") (pinfunction "2_2") (pintype "passive"))
      (node (ref "R330") (pin "1") (pinfunction "1_1") (pintype "passive"))
      (node (ref "R331") (pin "2") (pinfunction "2_2") (pintype "passive"))
      (node (ref "U300") (pin "22") (pinfunction "RXD3/PHYAD0_22") (pintype "output"))
    )
    (net (code "62") (name "CHASIS") (class "Default")
      (node (ref "C314") (pin "1") (pinfunction "1_1") (pintype "passive"))
      (node (ref "C315") (pin "1") (pinfunction "1_1") (pintype "passive"))
      (node (ref "CON300") (pin "15") (pinfunction "SH1_15") (pintype "power_in"))
      (node (ref "CON300") (pin "16") (pinfunction "SH2_16") (pintype "power_in"))
      (node (ref "L301") (pin "1") (pinfunction "1_1") (pintype "passive"))
    )
    (net (code "63") (name "GND") (class "Default")
      (node (ref "C300") (pin "2") (pinfunction "2_2") (pintype "passive"))
      (node (ref "C301") (pin "1") (pinfunction "1_1") (pintype "passive"))
      (node (ref "C302") (pin "1") (pinfunction "1_1") (pintype "passive"))
      (node (ref "C303") (pin "1") (pinfunction "1_1") (pintype "passive"))
      (node (ref "C304") (pin "2") (pinfunction "2_2") (pintype "passive"))
      (node (ref "C305") (pin "2") (pinfunction "2_2") (pintype "passive"))
      (node (ref "C306") (pin "2") (pinfunction "2_2") (pintype "passive"))
      (node (ref "C307") (pin "2") (pinfunction "2_2") (pintype "passive"))
      (node (ref "C308") (pin "1") (pinfunction "1_1") (pintype "passive"))
      (node (ref "C309") (pin "2") (pinfunction "2_2") (pintype "passive"))
      (node (ref "C310") (pin "2") (pinfunction "2_2") (pintype "passive"))
      (node (ref "C311") (pin "1") (pinfunction "1_1") (pintype "passive"))
      (node (ref "C312") (pin "2") (pinfunction "2_2") (pintype "passive"))
      (node (ref "C313") (pin "1") (pinfunction "1_1") (pintype "passive"))
      (node (ref "C314") (pin "2") (pinfunction "2_2") (pintype "passive"))
      (node (ref "C315") (pin "2") (pinfunction "2_2") (pintype "passive"))
      (node (ref "C316") (pin "2") (pinfunction "2_2") (pintype "passive"))
      (node (ref "C317") (pin "2") (pinfunction "2_2") (pintype "passive"))
      (node (ref "CON300") (pin "1") (pinfunction "1_1") (pintype "passive"))
      (node (ref "L301") (pin "2") (pinfunction "2_2") (pintype "passive"))
      (node (ref "R303") (pin "1") (pinfunction "1_1") (pintype "passive"))
      (node (ref "R310") (pin "1") (pinfunction "1_1") (pintype "passive"))
      (node (ref "R312") (pin "2") (pinfunction "2_2") (pintype "passive"))
      (node (ref "R313") (pin "2") (pinfunction "2_2") (pintype "passive"))
      (node (ref "R314") (pin "2") (pinfunction "2_2") (pintype "passive"))
      (node (ref "R315") (pin "1") (pinfunction "1_1") (pintype "passive"))
      (node (ref "R319") (pin "1") (pinfunction "1_1") (pintype "passive"))
      (node (ref "R330") (pin "2") (pinfunction "2_2") (pintype "passive"))
      (node (ref "R332") (pin "2") (pinfunction "2_2") (pintype "passive"))
      (node (ref "R334") (pin "2") (pinfunction "2_2") (pintype "passive"))
      (node (ref "R336") (pin "2") (pinfunction "2_2") (pintype "passive"))
      (node (ref "R341") (pin "2") (pinfunction "2_2") (pintype "passive"))
      (node (ref "R343") (pin "2") (pinfunction "2_2") (pintype "passive"))
      (node (ref "TP301") (pin "1") (pinfunction "1_1") (pintype "passive"))
      (node (ref "U300") (pin "41") (pinfunction "GND_(EXPOSED_PAD)_41") (pintype "power_in"))
      (node (ref "X300") (pin "2") (pinfunction "GND1_2") (pintype "power_in"))
      (node (ref "X300") (pin "4") (pinfunction "GND2_4") (pintype "power_in"))
    )
    (net (code "64") (name "Net-(C301-Pad2)") (class "Default")
      (node (ref "C301") (pin "2") (pinfunction "2_2") (pintype "passive"))
      (node (ref "R320") (pin "1") (pinfunction "1_1") (pintype "passive"))
      (node (ref "X300") (pin "1") (pinfunction "1_1") (pintype "passive"))
    )
    (net (code "65") (name "Net-(C305-Pad1)") (class "Default")
      (node (ref "C305") (pin "1") (pinfunction "1_1") (pintype "passive"))
      (node (ref "C306") (pin "1") (pinfunction "1_1") (pintype "passive"))
      (node (ref "L300") (pin "2") (pinfunction "2_2") (pintype "passive"))
      (node (ref "R321") (pin "1") (pinfunction "1_1") (pintype "passive"))
      (node (ref "R322") (pin "2") (pinfunction "2_2") (pintype "passive"))
      (node (ref "R324") (pin "2") (pinfunction "2_2") (pintype "passive"))
    )
    (net (code "66") (name "Net-(D300-A)") (class "Default")
      (node (ref "D300") (pin "1") (pinfunction "A_1") (pintype "passive"))
      (node (ref "R311") (pin "1") (pinfunction "1_1") (pintype "passive"))
      (node (ref "R318") (pin "1") (pinfunction "1_1") (pintype "passive"))
    )
    (net (code "67") (name "Net-(D300-K)") (class "Default")
      (node (ref "D300") (pin "2") (pinfunction "K_2") (pintype "passive"))
      (node (ref "R317") (pin "1") (pinfunction "1_1") (pintype "passive"))
      (node (ref "R319") (pin "2") (pinfunction "2_2") (pintype "passive"))
    )
    (net (code "68") (name "Net-(L302-Pad1)") (class "Default")
      (node (ref "L302") (pin "1") (pinfunction "1_1") (pintype "passive"))
      (node (ref "L303") (pin "1") (pinfunction "1_1") (pintype "passive"))
      (node (ref "R345") (pin "2") (pinfunction "2_2") (pintype "passive"))
      (node (ref "R346") (pin "2") (pinfunction "2_2") (pintype "passive"))
    )
    (net (code "69") (name "Net-(Q300-B)") (class "Default")
      (node (ref "Q300") (pin "1") (pinfunction "B_1") (pintype "passive"))
      (node (ref "R339") (pin "1") (pinfunction "1_1") (pintype "passive"))
    )
    (net (code "70") (name "Net-(Q300-C)") (class "Default")
      (node (ref "Q300") (pin "3") (pinfunction "C_3") (pintype "passive"))
      (node (ref "R338") (pin "1") (pinfunction "1_1") (pintype "passive"))
      (node (ref "U300") (pin "12") (pinfunction "PHYRSTB_12") (pintype "input"))
    )
    (net (code "71") (name "Net-(U300-CLKOUT)") (class "Default")
      (node (ref "TP300") (pin "1") (pinfunction "1_1") (pintype "passive"))
      (node (ref "U300") (pin "35") (pinfunction "CLKOUT_35") (pintype "passive"))
    )
    (net (code "72") (name "Net-(U300-LED0{slash}CFG_EXT)") (class "Default")
      (node (ref "R306") (pin "2") (pinfunction "2_2") (pintype "passive"))
      (node (ref "R311") (pin "2") (pinfunction "2_2") (pintype "passive"))
      (node (ref "R314") (pin "1") (pinfunction "1_1") (pintype "passive"))
      (node (ref "R317") (pin "2") (pinfunction "2_2") (pintype "passive"))
      (node (ref "U300") (pin "32") (pinfunction "LED0/CFG_EXT_32") (pintype "output"))
    )
    (net (code "73") (name "Net-(U300-LED1{slash}CFG_LDO0)") (class "Default")
      (node (ref "R305") (pin "2") (pinfunction "2_2") (pintype "passive"))
      (node (ref "R307") (pin "2") (pinfunction "2_2") (pintype "passive"))
      (node (ref "R308") (pin "2") (pinfunction "2_2") (pintype "passive"))
      (node (ref "R313") (pin "1") (pinfunction "1_1") (pintype "passive"))
      (node (ref "U300") (pin "33") (pinfunction "LED1/CFG_LDO0_33") (pintype "output"))
    )
    (net (code "74") (name "Net-(U300-LED2{slash}CFG_LDO1)") (class "Default")
      (node (ref "R300") (pin "2") (pinfunction "2_2") (pintype "passive"))
      (node (ref "R301") (pin "2") (pinfunction "2_2") (pintype "passive"))
      (node (ref "R304") (pin "2") (pinfunction "2_2") (pintype "passive"))
      (node (ref "R312") (pin "1") (pinfunction "1_1") (pintype "passive"))
      (node (ref "U300") (pin "34") (pinfunction "LED2/CFG_LDO1_34") (pintype "output"))
    )
    (net (code "75") (name "Net-(U300-REG_OUT{slash}LDO_OUT)") (class "Default")
      (node (ref "C304") (pin "1") (pinfunction "1_1") (pintype "passive"))
      (node (ref "L300") (pin "1") (pinfunction "1_1") (pintype "passive"))
      (node (ref "R321") (pin "2") (pinfunction "2_2") (pintype "passive"))
      (node (ref "U300") (pin "30") (pinfunction "REG_OUT/LDO_OUT_30") (pintype "output"))
    )
    (net (code "76") (name "Net-(U300-RSET)") (class "Default")
      (node (ref "R315") (pin "2") (pinfunction "2_2") (pintype "passive"))
      (node (ref "U300") (pin "39") (pinfunction "RSET_39") (pintype "output"))
    )
    (net (code "77") (name "Net-(U300-XTAL_IN)") (class "Default")
      (node (ref "C300") (pin "1") (pinfunction "1_1") (pintype "passive"))
      (node (ref "U300") (pin "36") (pinfunction "XTAL_IN_36") (pintype "passive"))
      (node (ref "X300") (pin "3") (pinfunction "3_3") (pintype "passive"))
    )
    (net (code "78") (name "Net-(U300-XTAL_OUT{slash}EXT_CLK)") (class "Default")
      (node (ref "R320") (pin "2") (pinfunction "2_2") (pintype "passive"))
      (node (ref "U300") (pin "37") (pinfunction "XTAL_OUT/EXT_CLK_37") (pintype "passive"))
    )
    (net (code "79") (name "unconnected-(CON300-Pad2)") (class "Default")
      (node (ref "CON300") (pin "2") (pinfunction "2_2") (pintype "passive"))
    )
  )
)
